# as5600_tiny_3v3.net
KiCad netlist of a schematic drawn in EAGLE
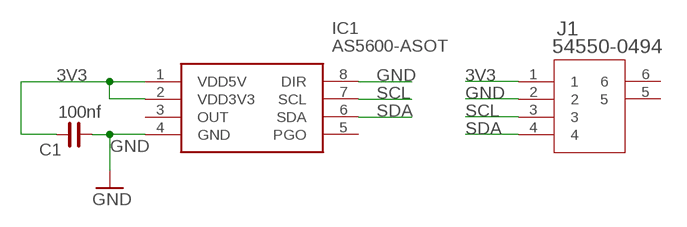
[diagram p0: schematic, sheet 1]

(export (version "E")
  (design (tool "Eeschema 10.0.6"))
  (components
    (comp (ref "C1")
      (value "100nf")
      (footprint "eagle-import:C0603")
      (libsource (lib "eagle-import") (part "C_0603"))
    )
    (comp (ref "IC1")
      (value "AS5600-ASOT")
      (footprint "eagle-import:SOIC127P600X175-8N")
      (fields (field (name "MOUSER_PART_NUMBER") "985-AS5600-ASOT"))
      (libsource (lib "eagle-import") (part "AS5600-ASOT"))
    )
    (comp (ref "J1")
      (value "54550-0494")
      (footprint "eagle-import:CON4_1X4_DRB2_MOL")
      (libsource (lib "eagle-import") (part "54550-0494"))
    )
  )
  (nets
    (net (code "1") (name "/3V3") (class "Default")
      (node (ref "C1") (pin "2") (pinfunction "2_2") (pintype "passive"))
      (node (ref "IC1") (pin "1") (pinfunction "VDD5V_1") (pintype "bidirectional"))
      (node (ref "IC1") (pin "2") (pinfunction "VDD3V3_2") (pintype "bidirectional"))
      (node (ref "J1") (pin "1") (pinfunction "1_1") (pintype "passive"))
    )
    (net (code "2") (name "/SCL") (class "Default")
      (node (ref "IC1") (pin "7") (pinfunction "SCL_7") (pintype "bidirectional"))
      (node (ref "J1") (pin "3") (pinfunction "3_3") (pintype "passive"))
    )
    (net (code "3") (name "/SDA") (class "Default")
      (node (ref "IC1") (pin "6") (pinfunction "SDA_6") (pintype "bidirectional"))
      (node (ref "J1") (pin "4") (pinfunction "4_4") (pintype "passive"))
    )
    (net (code "4") (name "GND") (class "Default")
      (node (ref "C1") (pin "1") (pinfunction "1_1") (pintype "passive"))
      (node (ref "IC1") (pin "4") (pinfunction "GND_4") (pintype "bidirectional"))
      (node (ref "IC1") (pin "8") (pinfunction "DIR_8") (pintype "bidirectional"))
      (node (ref "J1") (pin "2") (pinfunction "2_2") (pintype "passive"))
    )
    (net (code "5") (name "unconnected-(IC1-OUT-Pad3)") (class "Default")
      (node (ref "IC1") (pin "3") (pinfunction "OUT_3") (pintype "bidirectional"))
    )
    (net (code "6") (name "unconnected-(IC1-PGO-Pad5)") (class "Default")
      (node (ref "IC1") (pin "5") (pinfunction "PGO_5") (pintype "bidirectional"))
    )
    (net (code "7") (name "unconnected-(J1-Pad5)") (class "Default")
      (node (ref "J1") (pin "5") (pinfunction "5_5") (pintype "passive"))
    )
    (net (code "8") (name "unconnected-(J1-Pad6)") (class "Default")
      (node (ref "J1") (pin "6") (pinfunction "6_6") (pintype "passive"))
    )
  )
)
